# 5v_power.net
KiCad netlist of a schematic drawn in Altium Designer
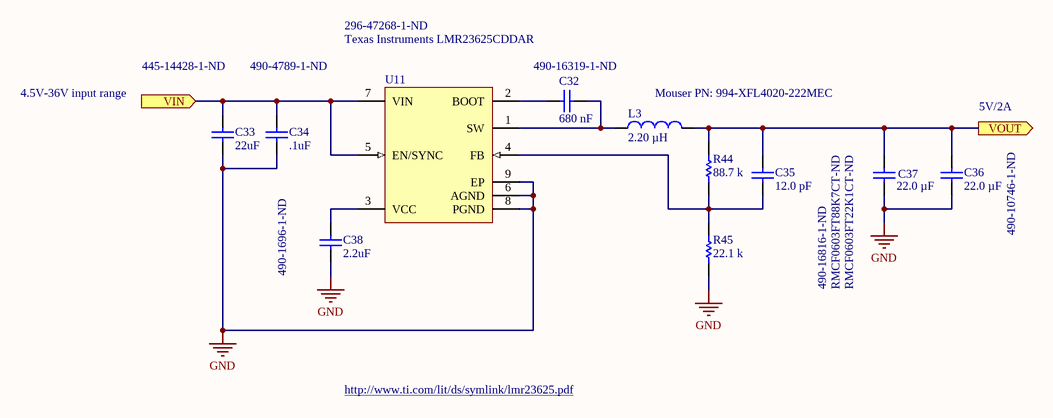
[diagram p0: 5v_power.SchDoc]

(export (version "E")
  (design (tool "Eeschema 10.0.6"))
  (components
    (comp (ref "C32")
      (value "Murata GRM21BR71H684KAC4L")
      (footprint "PCB-xrh88671zmf2jss4mnlt-1")
      (description "Cap Ceramic 0.68uF 50V X7R 10% Pad SMD 0805 125C T/R")
      (fields
        (field (name "MANUFACTURER PART NUMBER") "GRM21BR71H684KAC4L")
        (field (name "CAPACITANCE") "680 nF")
      )
      (libsource (lib "CommunityVault") (part "CMP-44008e6100d59bc7-1"))
    )
    (comp (ref "C33")
      (value "Cap")
      (footprint "PCB-lllx3wppxbec679u3f24-1")
      (description "C Series 0805 22 uF 35 V ±20 % Tolerance X5R SMT Multilayer Ceramic Capacitor")
      (fields
        (field (name "MANUFACTURER PART NUMBER") "C2012X5R1V226M125AC")
        (field (name "CAPACITANCE") "22uF")
      )
      (libsource (lib "CommunityVault") (part "CMP-0d44c5e3fbabd283-1"))
    )
    (comp (ref "C34")
      (value "Murata GCM21BR72A104KA37L")
      (footprint "CAPC2013X140X45ML15T25")
      (description "CAP CER 0.1UF 100V 10% X7R 0805")
      (fields (field (name "CAPACITANCE") ".1uF"))
      (libsource (lib "CommunityVault") (part "CMP-120358-2"))
    )
    (comp (ref "C35")
      (value "Murata GRM21A5C2D120JW01D")
      (footprint "PCB-xrh88671zmf2jss4mnlt-1")
      (description "Cap Ceramic 12pF 200V C0G 5% SMD 0805 125°C Paper T/R")
      (fields
        (field (name "MANUFACTURER PART NUMBER") "GRM21A5C2D120JW01D")
        (field (name "CAPACITANCE") "12.0 pF")
      )
      (libsource (lib "CommunityVault") (part "CMP-50dd9b1f09f28f1a-1"))
    )
    (comp (ref "C36")
      (value "Murata GRM21BR61A226ME44L")
      (footprint "PCB-xrh88671zmf2jss4mnlt-1")
      (description "0805 22 uF 10 V ±20% Tolerance X5R Multilayer Ceramic Chip Capacitor")
      (fields
        (field (name "MANUFACTURER PART NUMBER") "GRM21BR61A226ME44L")
        (field (name "CAPACITANCE") "22.0 µF")
      )
      (libsource (lib "CommunityVault") (part "CMP-7d69b6ab24aca2ae-1"))
    )
    (comp (ref "C37")
      (value "Murata GRM21BR61A226ME44L")
      (footprint "PCB-xrh88671zmf2jss4mnlt-1")
      (description "0805 22 uF 10 V ±20% Tolerance X5R Multilayer Ceramic Chip Capacitor")
      (fields
        (field (name "MANUFACTURER PART NUMBER") "GRM21BR61A226ME44L")
        (field (name "CAPACITANCE") "22.0 µF")
      )
      (libsource (lib "CommunityVault") (part "CMP-7d69b6ab24aca2ae-1"))
    )
    (comp (ref "C38")
      (value "Murata GRM21BR71A225KA01L")
      (footprint "CAPC2013X135X50LL10T20")
      (description "CAP CER 2.2UF 10V 10% X7R 0805")
      (fields (field (name "CAPACITANCE") "2.2uF"))
      (libsource (lib "CommunityVault") (part "CMP-19299739-2"))
    )
    (comp (ref "L3")
      (value "Coilcraft XFL4020-222MEC")
      (footprint "PCB-9d9k809zadibtjsjgh1m-1")
      (description "Power inductor, shielded, 20% tol, SMT, RoHS, halogen free")
      (fields
        (field (name "MANUFACTURER PART NUMBER") "XFL4020-222MEC")
        (field (name "INDUCTANCE") "2.20 µH")
      )
      (libsource (lib "CommunityVault") (part "CMP-3796fe24315fe851-1"))
    )
    (comp (ref "R44")
      (value "Stackpole Electronics RMCF0603FT88K7")
      (footprint "PCB-9ahxsq8gddjqcnfjmojj-1")
      (description "RMCF Series 0603 0.1 W 88.7 kOhm ±1 % ±100 ppm/°C SMT Thick Film Chip Resistor")
      (fields (field (name "MANUFACTURER PART NUMBER") "RMCF0603FT88K7") (field (name "RESISTANCE") "88.7 k"))
      (libsource (lib "CommunityVault") (part "CMP-fc30341ff50423f7-1"))
    )
    (comp (ref "R45")
      (value "Stackpole Electronics RMCF0603FT22K1")
      (footprint "PCB-9ahxsq8gddjqcnfjmojj-1")
      (description "RMCF Series 0603 0.1 W 22.1 kOhm ±1 % ±100 ppm/°C SMT Thick Film Chip Resistor")
      (fields (field (name "MANUFACTURER PART NUMBER") "RMCF0603FT22K1") (field (name "RESISTANCE") "22.1 k"))
      (libsource (lib "CommunityVault") (part "CMP-f875305af60927b2-1"))
    )
    (comp (ref "U11")
      (value "Texas Instruments LMR23625CDDAR")
      (footprint "PCB-d70mjtd98i3vq9jo7u2s-1")
      (description "SIMPLE SWITCHER?, 36V 2.5A Synchronous Step-Down Converter 8-SO PowerPAD -40 to 125")
      (fields (field (name "MANUFACTURER PART NUMBER") "LMR23625CDDAR"))
      (libsource (lib "CommunityVault") (part "SYM-9dcb50cfc7eb420c-1"))
    )
  )
  (nets
    (net (code "1") (name "/VIN") (class "Default")
      (node (ref "C33") (pin "1") (pinfunction "1_1") (pintype "passive"))
      (node (ref "C34") (pin "1") (pinfunction "1_1") (pintype "passive"))
      (node (ref "U11") (pin "5") (pinfunction "EN/SYNC_5") (pintype "input"))
      (node (ref "U11") (pin "7") (pinfunction "VIN_7") (pintype "power_in"))
    )
    (net (code "2") (name "/VOUT") (class "Default")
      (node (ref "C35") (pin "2") (pinfunction "2_2") (pintype "passive"))
      (node (ref "C36") (pin "2") (pinfunction "2_2") (pintype "passive"))
      (node (ref "C37") (pin "2") (pinfunction "2_2") (pintype "passive"))
      (node (ref "L3") (pin "2") (pinfunction "2_2") (pintype "passive"))
      (node (ref "R44") (pin "1") (pinfunction "1_1") (pintype "passive"))
    )
    (net (code "3") (name "GND") (class "Default")
      (node (ref "C33") (pin "2") (pinfunction "2_2") (pintype "passive"))
      (node (ref "C34") (pin "2") (pinfunction "2_2") (pintype "passive"))
      (node (ref "C36") (pin "1") (pinfunction "1_1") (pintype "passive"))
      (node (ref "C37") (pin "1") (pinfunction "1_1") (pintype "passive"))
      (node (ref "C38") (pin "1") (pinfunction "1_1") (pintype "passive"))
      (node (ref "R45") (pin "1") (pinfunction "1_1") (pintype "passive"))
      (node (ref "U11") (pin "6") (pinfunction "AGND_6") (pintype "power_in"))
      (node (ref "U11") (pin "8") (pinfunction "PGND_8") (pintype "power_in"))
      (node (ref "U11") (pin "9") (pinfunction "EP_9") (pintype "power_in"))
    )
    (net (code "4") (name "Net-(U11-BOOT)") (class "Default")
      (node (ref "C32") (pin "2") (pinfunction "2_2") (pintype "passive"))
      (node (ref "U11") (pin "2") (pinfunction "BOOT_2") (pintype "passive"))
    )
    (net (code "5") (name "Net-(U11-FB)") (class "Default")
      (node (ref "C35") (pin "1") (pinfunction "1_1") (pintype "passive"))
      (node (ref "R44") (pin "2") (pinfunction "2_2") (pintype "passive"))
      (node (ref "R45") (pin "2") (pinfunction "2_2") (pintype "passive"))
      (node (ref "U11") (pin "4") (pinfunction "FB_4") (pintype "input"))
    )
    (net (code "6") (name "Net-(U11-SW)") (class "Default")
      (node (ref "C32") (pin "1") (pinfunction "1_1") (pintype "passive"))
      (node (ref "L3") (pin "1") (pinfunction "1_1") (pintype "passive"))
      (node (ref "U11") (pin "1") (pinfunction "SW_1") (pintype "power_in"))
    )
    (net (code "7") (name "Net-(U11-VCC)") (class "Default")
      (node (ref "C38") (pin "2") (pinfunction "2_2") (pintype "passive"))
      (node (ref "U11") (pin "3") (pinfunction "VCC_3") (pintype "power_in"))
    )
  )
)
